# Aula_02.net
KiCad netlist of a schematic drawn in EAGLE
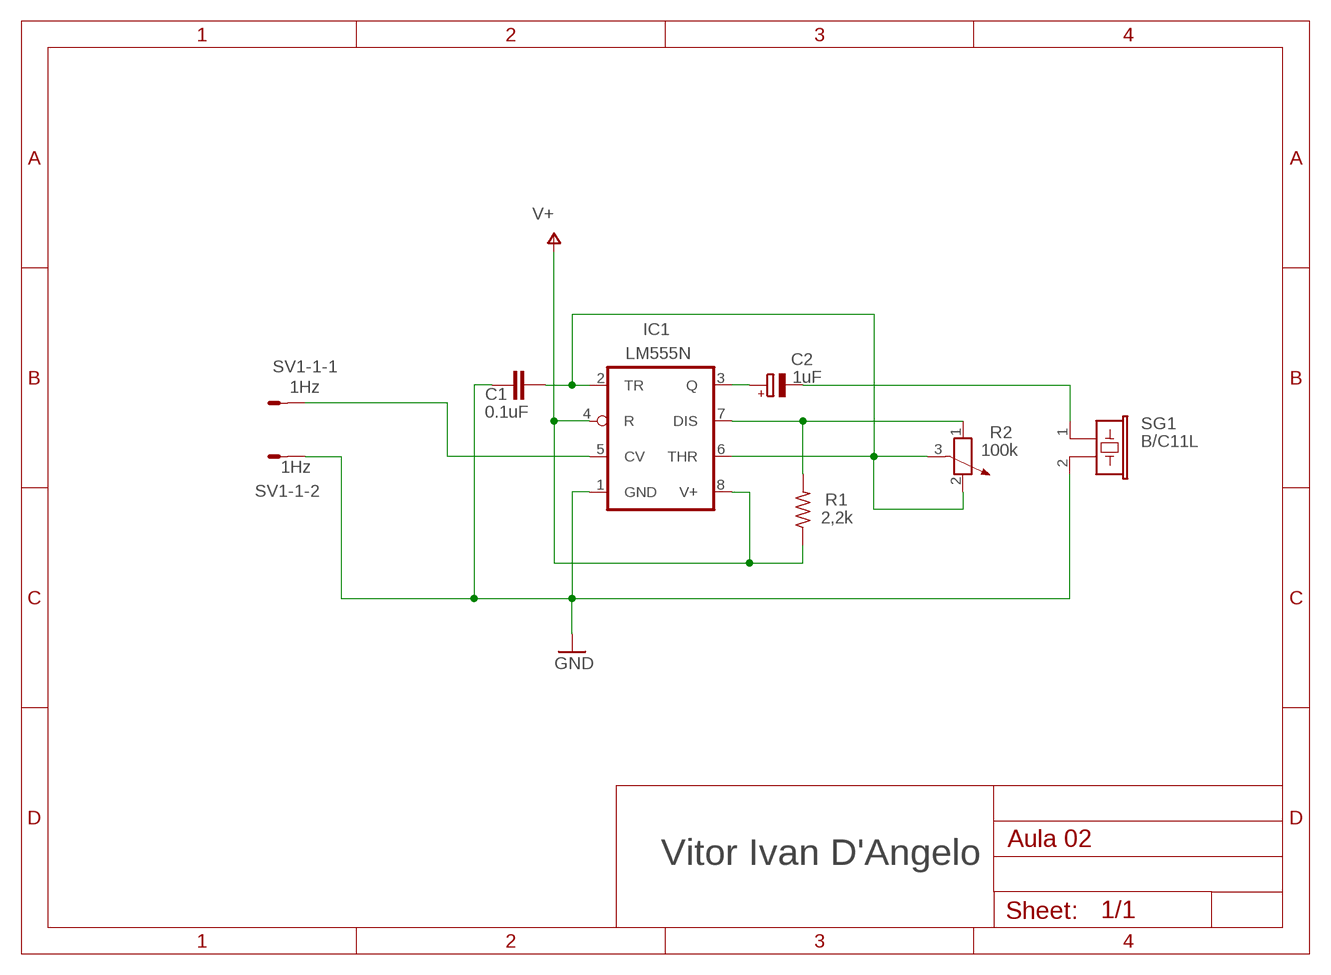
[diagram p0: schematic, sheet 1]

(export (version "E")
  (design (tool "Eeschema 10.0.6"))
  (components
    (comp (ref "C1")
      (value "0.1uF")
      (footprint "eagle-import:C025-040X050")
      (libsource (lib "eagle-import") (part "C-EU025-040X050"))
    )
    (comp (ref "C2")
      (value "1uF")
      (footprint "eagle-import:E2-5")
      (libsource (lib "eagle-import") (part "CPOL-EUE2-5"))
    )
    (comp (ref "IC1")
      (value "LM555N")
      (footprint "eagle-import:DIL08")
      (libsource (lib "eagle-import") (part "555NLM"))
    )
    (comp (ref "R1")
      (value "2,2k")
      (footprint "eagle-import:0204_7")
      (libsource (lib "eagle-import") (part "R-US_0204/7"))
    )
    (comp (ref "R2")
      (value "100k")
      (footprint "eagle-import:PT-10")
      (libsource (lib "eagle-import") (part "POTENTIOMETER_PT-10"))
    )
    (comp (ref "SG1")
      (value "B/C11L")
      (footprint "eagle-import:B_C11L")
      (libsource (lib "eagle-import") (part "B/C11L"))
    )
    (comp (ref "SV1-1")
      (value "1Hz")
      (footprint "eagle-import:L02P")
      (libsource (lib "eagle-import") (part "L02P"))
    )
  )
  (nets
    (net (code "1") (name "GND") (class "Default")
      (node (ref "C1") (pin "1") (pinfunction "1_1") (pintype "passive"))
      (node (ref "IC1") (pin "1") (pinfunction "GND_1") (pintype "power_in"))
      (node (ref "SG1") (pin "2") (pinfunction "2_2") (pintype "passive"))
      (node (ref "SV1-1") (pin "2") (pinfunction "S_2") (pintype "passive"))
    )
    (net (code "2") (name "Net-(C2-Pad-)") (class "Default")
      (node (ref "C2") (pin "-") (pinfunction "-_-") (pintype "passive"))
      (node (ref "SG1") (pin "1") (pinfunction "1_1") (pintype "passive"))
    )
    (net (code "3") (name "Net-(IC1-CV)") (class "Default")
      (node (ref "IC1") (pin "5") (pinfunction "CV_5") (pintype "input"))
      (node (ref "SV1-1") (pin "1") (pinfunction "S_1") (pintype "passive"))
    )
    (net (code "4") (name "Net-(IC1-DIS)") (class "Default")
      (node (ref "IC1") (pin "7") (pinfunction "DIS_7") (pintype "input"))
      (node (ref "R1") (pin "2") (pinfunction "2_2") (pintype "passive"))
      (node (ref "R2") (pin "1") (pinfunction "1_1") (pintype "passive"))
    )
    (net (code "5") (name "Net-(IC1-Q)") (class "Default")
      (node (ref "C2") (pin "+") (pinfunction "+_+") (pintype "passive"))
      (node (ref "IC1") (pin "3") (pinfunction "Q_3") (pintype "output"))
    )
    (net (code "6") (name "Net-(IC1-THR)") (class "Default")
      (node (ref "C1") (pin "2") (pinfunction "2_2") (pintype "passive"))
      (node (ref "IC1") (pin "2") (pinfunction "TR_2") (pintype "input"))
      (node (ref "IC1") (pin "6") (pinfunction "THR_6") (pintype "input"))
      (node (ref "R2") (pin "2") (pinfunction "2_2") (pintype "passive"))
      (node (ref "R2") (pin "3") (pinfunction "3_3") (pintype "passive"))
    )
    (net (code "7") (name "V+") (class "Default")
      (node (ref "IC1") (pin "4") (pinfunction "R_4") (pintype "input"))
      (node (ref "IC1") (pin "8") (pinfunction "V+_8") (pintype "power_in"))
      (node (ref "R1") (pin "1") (pinfunction "1_1") (pintype "passive"))
    )
  )
)
